# USB_UART.net
KiCad netlist of a schematic drawn in Altium Designer
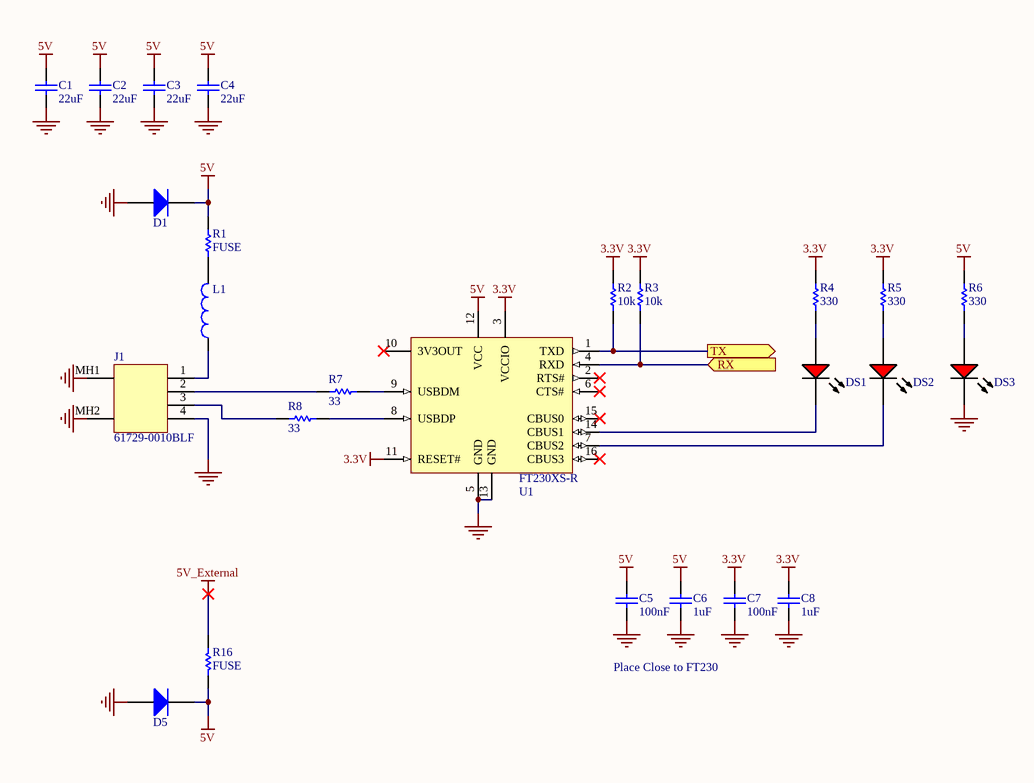
[diagram p0: USB_UART.SchDoc]

(export (version "E")
  (design (tool "Eeschema 10.0.6"))
  (components
    (comp (ref "C1")
      (value "22uF")
      (footprint "CAPC1206(3216)190_M")
      (fields (field (name "TOLERANCE") "Â±20%"))
      (libsource (lib "Altium Content Vault") (part "CAP"))
    )
    (comp (ref "C2")
      (value "22uF")
      (footprint "CAPC1206(3216)190_M")
      (fields (field (name "TOLERANCE") "Â±20%"))
      (libsource (lib "Altium Content Vault") (part "CAP"))
    )
    (comp (ref "C3")
      (value "22uF")
      (footprint "CAPC1206(3216)190_M")
      (fields (field (name "TOLERANCE") "Â±20%"))
      (libsource (lib "Altium Content Vault") (part "CAP"))
    )
    (comp (ref "C4")
      (value "22uF")
      (footprint "CAPC1206(3216)190_M")
      (fields (field (name "TOLERANCE") "Â±20%"))
      (libsource (lib "Altium Content Vault") (part "CAP"))
    )
    (comp (ref "C5")
      (value "100nF")
      (footprint "CAPC0805(2012)145_N")
      (fields (field (name "TOLERANCE") "Â±20%"))
      (libsource (lib "Altium Content Vault") (part "CAP"))
    )
    (comp (ref "C6")
      (value "1uF")
      (footprint "CAPC0805(2012)145_N")
      (fields (field (name "TOLERANCE") "Â±20%"))
      (libsource (lib "Altium Content Vault") (part "CAP"))
    )
    (comp (ref "C7")
      (value "100nF")
      (footprint "CAPC0805(2012)145_N")
      (fields (field (name "TOLERANCE") "Â±20%"))
      (libsource (lib "Altium Content Vault") (part "CAP"))
    )
    (comp (ref "C8")
      (value "1uF")
      (footprint "CAPC0805(2012)145_N")
      (fields (field (name "TOLERANCE") "Â±20%"))
      (libsource (lib "Altium Content Vault") (part "CAP"))
    )
    (comp (ref "D1")
      (value "MMSD4148T3G")
      (footprint "ONSC-SOD123-2-425G-04_V")
      (fields (field (name "MANUFACTURER") "ON Semiconductor"))
      (libsource (lib "Altium Content Vault") (part "ONSC-MMSD4148-SOD123-2"))
    )
    (comp (ref "D5")
      (value "MMSD4148T3G")
      (footprint "ONSC-SOD123-2-425G-04_V")
      (fields (field (name "MANUFACTURER") "ON Semiconductor"))
      (libsource (lib "Altium Content Vault") (part "ONSC-MMSD4148-SOD123-2"))
    )
    (comp (ref "DS1")
      (value "TLMS1100-GS08")
      (footprint "VISH-TLMX1100_V")
      (description "LED, RED, 2.1 V, -40 to 100 degC, 2-Pin SMD (0603), RoHS, Tape and Reel")
      (fields (field (name "TOLERANCE") "5%"))
      (libsource (lib "Altium Content Vault") (part "LED-RED-AK-2"))
    )
    (comp (ref "DS2")
      (value "TLMS1100-GS08")
      (footprint "VISH-TLMX1100_V")
      (description "LED, RED, 2.1 V, -40 to 100 degC, 2-Pin SMD (0603), RoHS, Tape and Reel")
      (fields (field (name "TOLERANCE") "5%"))
      (libsource (lib "Altium Content Vault") (part "LED-RED-AK-2"))
    )
    (comp (ref "DS3")
      (value "TLMS1100-GS08")
      (footprint "VISH-TLMX1100_V")
      (description "LED, RED, 2.1 V, -40 to 100 degC, 2-Pin SMD (0603), RoHS, Tape and Reel")
      (fields (field (name "TOLERANCE") "5%"))
      (libsource (lib "Altium Content Vault") (part "LED-RED-AK-2"))
    )
    (comp (ref "J1")
      (value "61729-0010BLF")
      (footprint "FCI-61729-0010BLF-6_V")
      (description "Single USB 2.0, B Type, Right Angle Jack, Through Hole, RoHS, Tube")
      (fields (field (name "MANUFACTURER") "FCI Electronics"))
      (libsource (lib "Altium Content Vault") (part "FCI-CN-1F-R6"))
    )
    (comp (ref "L1")
      (value "FBMJ2125HM210NT")
      (footprint "INDC2013X105X50LL20T30")
      (description "Chip Inductor, 21 Ohm, +/- 30%, 6 A, -40 to 125 degC, 0805 (2012 Metric), RoHS, Tape and Reel")
      (fields (field (name "TOLERANCE") "30%"))
      (libsource (lib "Altium Content Vault") (part "IND-2"))
    )
    (comp (ref "R1")
      (value "FUSE")
      (footprint "RESC0805(2012)_M")
      (fields (field (name "POWER") "0.125 W") (field (name "TOLERANCE") "5 %"))
      (libsource (lib "Altium Content Vault") (part "RES"))
    )
    (comp (ref "R2")
      (value "10k")
      (footprint "RESC0805(2012)_M")
      (fields (field (name "POWER") "0.125 W") (field (name "TOLERANCE") "5 %"))
      (libsource (lib "Altium Content Vault") (part "RES"))
    )
    (comp (ref "R3")
      (value "10k")
      (footprint "RESC0805(2012)_M")
      (fields (field (name "POWER") "0.125 W") (field (name "TOLERANCE") "5 %"))
      (libsource (lib "Altium Content Vault") (part "RES"))
    )
    (comp (ref "R4")
      (value "330")
      (footprint "RESC0805(2012)_M")
      (fields (field (name "POWER") "0.125 W") (field (name "TOLERANCE") "5 %"))
      (libsource (lib "Altium Content Vault") (part "RES"))
    )
    (comp (ref "R5")
      (value "330")
      (footprint "RESC0805(2012)_M")
      (fields (field (name "POWER") "0.125 W") (field (name "TOLERANCE") "5 %"))
      (libsource (lib "Altium Content Vault") (part "RES"))
    )
    (comp (ref "R6")
      (value "330")
      (footprint "RESC0805(2012)_M")
      (fields (field (name "POWER") "0.125 W") (field (name "TOLERANCE") "5 %"))
      (libsource (lib "Altium Content Vault") (part "RES"))
    )
    (comp (ref "R7")
      (value "33")
      (footprint "RESC0805(2012)_M")
      (fields (field (name "POWER") "0.125 W") (field (name "TOLERANCE") "5 %"))
      (libsource (lib "Altium Content Vault") (part "RES"))
    )
    (comp (ref "R8")
      (value "33")
      (footprint "RESC0805(2012)_M")
      (fields (field (name "POWER") "0.125 W") (field (name "TOLERANCE") "5 %"))
      (libsource (lib "Altium Content Vault") (part "RES"))
    )
    (comp (ref "R16")
      (value "FUSE")
      (footprint "RESC0805(2012)_M")
      (fields (field (name "POWER") "0.125 W") (field (name "TOLERANCE") "5 %"))
      (libsource (lib "Altium Content Vault") (part "RES"))
    )
    (comp (ref "U1")
      (value "FT230XS-R")
      (footprint "SSOP-16_M")
      (fields (field (name "MANUFACTURER") "FTDI"))
      (libsource (lib "Altium Content Vault") (part "COM-USB-FT230XS-IL16"))
    )
  )
  (nets
    (net (code "1") (name "/RX") (class "Default")
      (node (ref "R3") (pin "1") (pinfunction "1_1") (pintype "passive"))
      (node (ref "U1") (pin "4") (pinfunction "RXD_4") (pintype "input"))
    )
    (net (code "2") (name "/TX") (class "Default")
      (node (ref "R2") (pin "1") (pinfunction "1_1") (pintype "passive"))
      (node (ref "U1") (pin "1") (pinfunction "TXD_1") (pintype "output"))
    )
    (net (code "3") (name "3.3V") (class "Default")
      (node (ref "C7") (pin "2") (pinfunction "2_2") (pintype "passive"))
      (node (ref "C8") (pin "2") (pinfunction "2_2") (pintype "passive"))
      (node (ref "R2") (pin "2") (pinfunction "2_2") (pintype "passive"))
      (node (ref "R3") (pin "2") (pinfunction "2_2") (pintype "passive"))
      (node (ref "R4") (pin "2") (pinfunction "2_2") (pintype "passive"))
      (node (ref "R5") (pin "2") (pinfunction "2_2") (pintype "passive"))
      (node (ref "U1") (pin "11") (pinfunction "RESET#_11") (pintype "input"))
      (node (ref "U1") (pin "3") (pinfunction "VCCIO_3") (pintype "power_in"))
    )
    (net (code "4") (name "5V") (class "Default")
      (node (ref "C1") (pin "2") (pinfunction "2_2") (pintype "passive"))
      (node (ref "C2") (pin "2") (pinfunction "2_2") (pintype "passive"))
      (node (ref "C3") (pin "2") (pinfunction "2_2") (pintype "passive"))
      (node (ref "C4") (pin "2") (pinfunction "2_2") (pintype "passive"))
      (node (ref "C5") (pin "2") (pinfunction "2_2") (pintype "passive"))
      (node (ref "C6") (pin "2") (pinfunction "2_2") (pintype "passive"))
      (node (ref "D1") (pin "1") (pinfunction "CATHODE_1") (pintype "passive"))
      (node (ref "D5") (pin "1") (pinfunction "CATHODE_1") (pintype "passive"))
      (node (ref "R1") (pin "2") (pinfunction "2_2") (pintype "passive"))
      (node (ref "R16") (pin "2") (pinfunction "2_2") (pintype "passive"))
      (node (ref "R6") (pin "2") (pinfunction "2_2") (pintype "passive"))
      (node (ref "U1") (pin "12") (pinfunction "VCC_12") (pintype "power_in"))
    )
    (net (code "5") (name "5V_External") (class "Default")
      (node (ref "R16") (pin "1") (pinfunction "1_1") (pintype "passive"))
    )
    (net (code "6") (name "GND") (class "Default")
      (node (ref "C1") (pin "1") (pinfunction "1_1") (pintype "passive"))
      (node (ref "C2") (pin "1") (pinfunction "1_1") (pintype "passive"))
      (node (ref "C3") (pin "1") (pinfunction "1_1") (pintype "passive"))
      (node (ref "C4") (pin "1") (pinfunction "1_1") (pintype "passive"))
      (node (ref "C5") (pin "1") (pinfunction "1_1") (pintype "passive"))
      (node (ref "C6") (pin "1") (pinfunction "1_1") (pintype "passive"))
      (node (ref "C7") (pin "1") (pinfunction "1_1") (pintype "passive"))
      (node (ref "C8") (pin "1") (pinfunction "1_1") (pintype "passive"))
      (node (ref "D1") (pin "2") (pinfunction "ANODE_2") (pintype "passive"))
      (node (ref "D5") (pin "2") (pinfunction "ANODE_2") (pintype "passive"))
      (node (ref "DS3") (pin "2") (pinfunction "K_2") (pintype "passive"))
      (node (ref "J1") (pin "4") (pinfunction "4_4") (pintype "passive"))
      (node (ref "J1") (pin "MH1") (pinfunction "MH1_MH1") (pintype "passive"))
      (node (ref "J1") (pin "MH2") (pinfunction "MH2_MH2") (pintype "passive"))
      (node (ref "U1") (pin "13") (pinfunction "GND_13") (pintype "power_in"))
      (node (ref "U1") (pin "5") (pinfunction "GND_5") (pintype "power_in"))
    )
    (net (code "7") (name "Net-(DS1-A)") (class "Default")
      (node (ref "DS1") (pin "1") (pinfunction "A_1") (pintype "passive"))
      (node (ref "R4") (pin "1") (pinfunction "1_1") (pintype "passive"))
    )
    (net (code "8") (name "Net-(DS1-K)") (class "Default")
      (node (ref "DS1") (pin "2") (pinfunction "K_2") (pintype "passive"))
      (node (ref "U1") (pin "14") (pinfunction "CBUS1_14") (pintype "bidirectional"))
    )
    (net (code "9") (name "Net-(DS2-A)") (class "Default")
      (node (ref "DS2") (pin "1") (pinfunction "A_1") (pintype "passive"))
      (node (ref "R5") (pin "1") (pinfunction "1_1") (pintype "passive"))
    )
    (net (code "10") (name "Net-(DS2-K)") (class "Default")
      (node (ref "DS2") (pin "2") (pinfunction "K_2") (pintype "passive"))
      (node (ref "U1") (pin "7") (pinfunction "CBUS2_7") (pintype "bidirectional"))
    )
    (net (code "11") (name "Net-(DS3-A)") (class "Default")
      (node (ref "DS3") (pin "1") (pinfunction "A_1") (pintype "passive"))
      (node (ref "R6") (pin "1") (pinfunction "1_1") (pintype "passive"))
    )
    (net (code "12") (name "Net-(J1-Pad1)") (class "Default")
      (node (ref "J1") (pin "1") (pinfunction "1_1") (pintype "passive"))
      (node (ref "L1") (pin "1") (pinfunction "1_1") (pintype "passive"))
    )
    (net (code "13") (name "Net-(J1-Pad2)") (class "Default")
      (node (ref "J1") (pin "2") (pinfunction "2_2") (pintype "passive"))
      (node (ref "R7") (pin "1") (pinfunction "1_1") (pintype "passive"))
    )
    (net (code "14") (name "Net-(J1-Pad3)") (class "Default")
      (node (ref "J1") (pin "3") (pinfunction "3_3") (pintype "passive"))
      (node (ref "R8") (pin "1") (pinfunction "1_1") (pintype "passive"))
    )
    (net (code "15") (name "Net-(L1-Pad2)") (class "Default")
      (node (ref "L1") (pin "2") (pinfunction "2_2") (pintype "passive"))
      (node (ref "R1") (pin "1") (pinfunction "1_1") (pintype "passive"))
    )
    (net (code "16") (name "Net-(U1-USBDM)") (class "Default")
      (node (ref "R7") (pin "2") (pinfunction "2_2") (pintype "passive"))
      (node (ref "U1") (pin "9") (pinfunction "USBDM_9") (pintype "input"))
    )
    (net (code "17") (name "Net-(U1-USBDP)") (class "Default")
      (node (ref "R8") (pin "2") (pinfunction "2_2") (pintype "passive"))
      (node (ref "U1") (pin "8") (pinfunction "USBDP_8") (pintype "input"))
    )
    (net (code "18") (name "unconnected-(U1-3V3OUT-Pad10)") (class "Default")
      (node (ref "U1") (pin "10") (pinfunction "3V3OUT_10") (pintype "power_in+no_connect"))
    )
    (net (code "19") (name "unconnected-(U1-CBUS0-Pad15)") (class "Default")
      (node (ref "U1") (pin "15") (pinfunction "CBUS0_15") (pintype "bidirectional+no_connect"))
    )
    (net (code "20") (name "unconnected-(U1-CBUS3-Pad16)") (class "Default")
      (node (ref "U1") (pin "16") (pinfunction "CBUS3_16") (pintype "bidirectional+no_connect"))
    )
    (net (code "21") (name "unconnected-(U1-CTS#-Pad6)") (class "Default")
      (node (ref "U1") (pin "6") (pinfunction "CTS#_6") (pintype "input+no_connect"))
    )
    (net (code "22") (name "unconnected-(U1-RTS#-Pad2)") (class "Default")
      (node (ref "U1") (pin "2") (pinfunction "RTS#_2") (pintype "output+no_connect"))
    )
  )
)
